# ARC-S-USB.net
KiCad netlist of a schematic drawn in Altium Designer
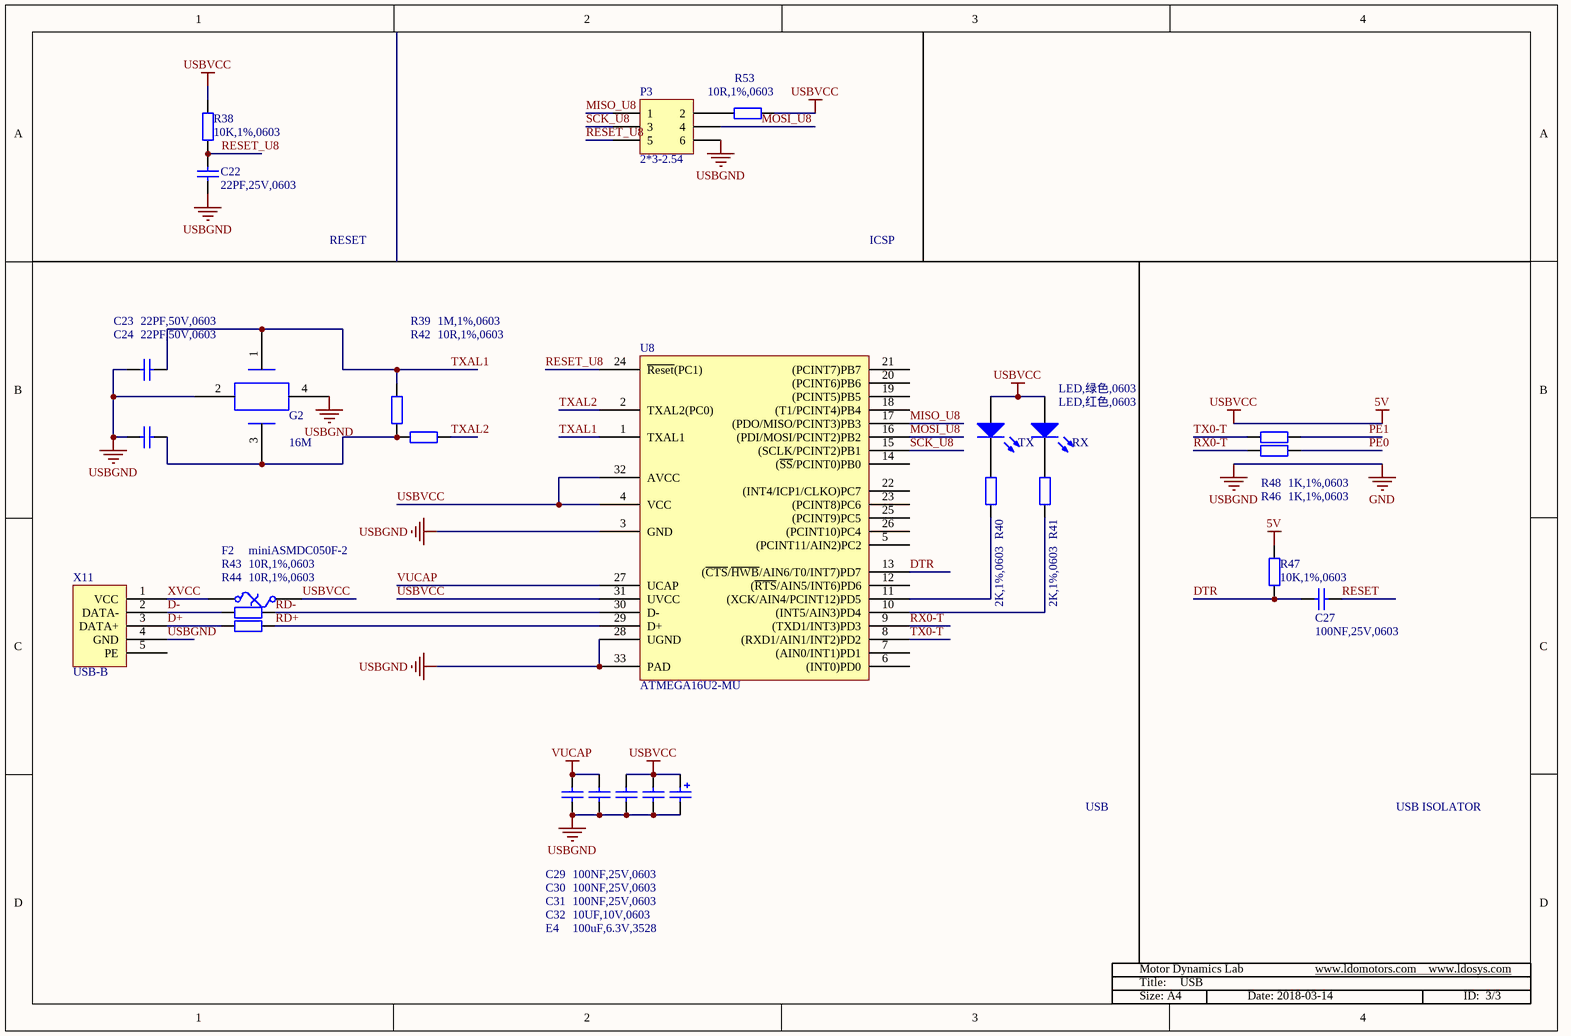
[diagram p0: ARC-S-USB.SchDoc]

(export (version "E")
  (design (tool "Eeschema 10.0.6"))
  (components
    (comp (ref "C22")
      (value "22PF,25V,0603")
      (footprint "RC0603")
      (description "Capacitor")
      (fields (field (name "PUBLISHER") "Altium Limited"))
      (libsource (lib "Miscellaneous Devices") (part "Cap"))
    )
    (comp (ref "C23")
      (value "22PF,50V,0603")
      (footprint "RC0603")
      (description "Capacitor")
      (fields (field (name "PUBLISHER") "Altium Limited"))
      (libsource (lib "Miscellaneous Devices") (part "Cap"))
    )
    (comp (ref "C24")
      (value "22PF,50V,0603")
      (footprint "RC0603")
      (description "Capacitor")
      (fields (field (name "PUBLISHER") "Altium Limited"))
      (libsource (lib "Miscellaneous Devices") (part "Cap"))
    )
    (comp (ref "C27")
      (value "100NF,25V,0603")
      (footprint "RC0603")
      (description "Capacitor")
      (fields (field (name "PUBLISHER") "Altium Limited"))
      (libsource (lib "Miscellaneous Devices") (part "Cap"))
    )
    (comp (ref "C29")
      (value "100NF,25V,0603")
      (footprint "RC0603")
      (description "Capacitor")
      (fields (field (name "PUBLISHER") "Altium Limited"))
      (libsource (lib "Miscellaneous Devices") (part "Cap"))
    )
    (comp (ref "C30")
      (value "100NF,25V,0603")
      (footprint "RC0603")
      (description "Capacitor")
      (fields (field (name "PUBLISHER") "Altium Limited"))
      (libsource (lib "Miscellaneous Devices") (part "Cap"))
    )
    (comp (ref "C31")
      (value "100NF,25V,0603")
      (footprint "RC0603")
      (description "Capacitor")
      (fields (field (name "PUBLISHER") "Altium Limited"))
      (libsource (lib "Miscellaneous Devices") (part "Cap"))
    )
    (comp (ref "C32")
      (value "10UF,10V,0603")
      (footprint "RC0603")
      (description "Capacitor")
      (fields (field (name "PUBLISHER") "Altium Limited"))
      (libsource (lib "Miscellaneous Devices") (part "Cap"))
    )
    (comp (ref "E4")
      (value "100uF,6.3V,3528")
      (footprint "3528-21")
      (description "Polarized Capacitor (Axial)")
      (fields (field (name "PUBLISHER") "Altium Limited"))
      (libsource (lib "Miscellaneous Devices") (part "Cap Pol2"))
    )
    (comp (ref "F2")
      (value "miniASMDC050F-2")
      (footprint "RC1812")
      (description "Thermal Fuse")
      (fields (field (name "PUBLISHER") "Altium Limited"))
      (libsource (lib "Miscellaneous Devices") (part "Fuse Thermal"))
    )
    (comp (ref "G2") (value "16M") (footprint "Y-3225") (libsource (lib "STM32F407VE") (part "G")))
    (comp (ref "P3")
      (value "2*3-2.54")
      (footprint "HDR2X3")
      (description "Header, 3-Pin, Dual row")
      (fields (field (name "PUBLISHER") "Altium Limited"))
      (libsource (lib "Miscellaneous Connectors") (part "Header 3X2"))
    )
    (comp (ref "R38")
      (value "10K,1%,0603")
      (footprint "RC0603")
      (description "Resistor")
      (fields (field (name "PUBLISHER") "Altium Limited"))
      (libsource (lib "") (part "Res2_3"))
    )
    (comp (ref "R39")
      (value "1M,1%,0603")
      (footprint "RC0603")
      (description "Resistor")
      (fields (field (name "PUBLISHER") "Altium Limited"))
      (libsource (lib "") (part "Res2_3"))
    )
    (comp (ref "R40")
      (value "2K,1%,0603")
      (footprint "RC0603")
      (description "Resistor")
      (fields (field (name "PUBLISHER") "Altium Limited"))
      (libsource (lib "") (part "Res2_3"))
    )
    (comp (ref "R41")
      (value "2K,1%,0603")
      (footprint "RC0603")
      (description "Resistor")
      (fields (field (name "PUBLISHER") "Altium Limited"))
      (libsource (lib "") (part "Res2_3"))
    )
    (comp (ref "R42")
      (value "10R,1%,0603")
      (footprint "RC0603")
      (description "Resistor")
      (fields (field (name "PUBLISHER") "Altium Limited"))
      (libsource (lib "Miscellaneous Devices") (part "Res2"))
    )
    (comp (ref "R43")
      (value "10R,1%,0603")
      (footprint "RC0603")
      (description "Resistor")
      (fields (field (name "PUBLISHER") "Altium Limited"))
      (libsource (lib "Miscellaneous Devices") (part "Res2"))
    )
    (comp (ref "R44")
      (value "10R,1%,0603")
      (footprint "RC0603")
      (description "Resistor")
      (fields (field (name "PUBLISHER") "Altium Limited"))
      (libsource (lib "Miscellaneous Devices") (part "Res2"))
    )
    (comp (ref "R46")
      (value "1K,1%,0603")
      (footprint "RC0603")
      (description "Resistor")
      (fields (field (name "PUBLISHER") "Altium Limited"))
      (libsource (lib "") (part "Res2_2"))
    )
    (comp (ref "R47")
      (value "10K,1%,0603")
      (footprint "RC0603")
      (description "Resistor")
      (fields (field (name "PUBLISHER") "Altium Limited"))
      (libsource (lib "") (part "Res2_1"))
    )
    (comp (ref "R48")
      (value "1K,1%,0603")
      (footprint "RC0603")
      (description "Resistor")
      (fields (field (name "PUBLISHER") "Altium Limited"))
      (libsource (lib "") (part "Res2_2"))
    )
    (comp (ref "R53")
      (value "10R,1%,0603")
      (footprint "RC0603")
      (description "Resistor")
      (fields (field (name "PUBLISHER") "Altium Limited"))
      (libsource (lib "") (part "Res2_2"))
    )
    (comp (ref "RX")
      (value "LED,红色,0603")
      (footprint "LED-0603")
      (description "Typical INFRARED GaAs LED")
      (fields (field (name "PUBLISHER") "Altium Limited"))
      (libsource (lib "Miscellaneous Devices") (part "LED0"))
    )
    (comp (ref "TX")
      (value "LED,绿色,0603")
      (footprint "LED-0603")
      (description "Typical INFRARED GaAs LED")
      (fields (field (name "PUBLISHER") "Altium Limited"))
      (libsource (lib "Miscellaneous Devices") (part "LED0"))
    )
    (comp (ref "U8")
      (value "ATMEGA16U2-MU")
      (footprint "QFN-32")
      (libsource (lib "LDO原理图库") (part "ATMEGA8U2-MU"))
    )
    (comp (ref "X11") (value "USB-B") (footprint "USB-B90") (libsource (lib "LDO原理图库") (part "B-USC")))
  )
  (nets
    (net (code "1") (name "/D+") (class "Default")
      (node (ref "R44") (pin "1") (pinfunction "1_1") (pintype "passive"))
      (node (ref "X11") (pin "3") (pinfunction "DATA+_3") (pintype "passive"))
    )
    (net (code "2") (name "/D-") (class "Default")
      (node (ref "R43") (pin "1") (pinfunction "1_1") (pintype "passive"))
      (node (ref "X11") (pin "2") (pinfunction "DATA-_2") (pintype "passive"))
    )
    (net (code "3") (name "/DTR") (class "Default")
      (node (ref "C27") (pin "2") (pinfunction "2_2") (pintype "passive"))
      (node (ref "R47") (pin "1") (pinfunction "1_1") (pintype "passive"))
      (node (ref "U8") (pin "13") (pinfunction "(~{CTS}/~{HWB}/AIN6/T0/INT7)PD7_13") (pintype "passive"))
    )
    (net (code "4") (name "/MISO_U8") (class "Default")
      (node (ref "P3") (pin "1") (pinfunction "1_1") (pintype "passive"))
      (node (ref "U8") (pin "17") (pinfunction "(PDO/MISO/PCINT3)PB3_17") (pintype "passive"))
    )
    (net (code "5") (name "/MOSI_U8") (class "Default")
      (node (ref "P3") (pin "4") (pinfunction "4_4") (pintype "passive"))
      (node (ref "U8") (pin "16") (pinfunction "(PDI/MOSI/PCINT2)PB2_16") (pintype "passive"))
    )
    (net (code "6") (name "/PE0") (class "Default")
      (node (ref "R46") (pin "1") (pinfunction "1_1") (pintype "passive"))
    )
    (net (code "7") (name "/PE1") (class "Default")
      (node (ref "R48") (pin "1") (pinfunction "1_1") (pintype "passive"))
    )
    (net (code "8") (name "/RD+") (class "Default")
      (node (ref "R44") (pin "2") (pinfunction "2_2") (pintype "passive"))
      (node (ref "U8") (pin "29") (pinfunction "D+_29") (pintype "passive"))
    )
    (net (code "9") (name "/RD-") (class "Default")
      (node (ref "R43") (pin "2") (pinfunction "2_2") (pintype "passive"))
      (node (ref "U8") (pin "30") (pinfunction "D-_30") (pintype "passive"))
    )
    (net (code "10") (name "/RESET") (class "Default")
      (node (ref "C27") (pin "1") (pinfunction "1_1") (pintype "passive"))
    )
    (net (code "11") (name "/RESET_U8") (class "Default")
      (node (ref "C22") (pin "1") (pinfunction "1_1") (pintype "passive"))
      (node (ref "P3") (pin "5") (pinfunction "5_5") (pintype "passive"))
      (node (ref "R38") (pin "2") (pinfunction "2_2") (pintype "passive"))
      (node (ref "U8") (pin "24") (pinfunction "~{Reset}(PC1)_24") (pintype "passive"))
    )
    (net (code "12") (name "/RX0-T") (class "Default")
      (node (ref "R46") (pin "2") (pinfunction "2_2") (pintype "passive"))
      (node (ref "U8") (pin "9") (pinfunction "(TXD1/INT3)PD3_9") (pintype "passive"))
    )
    (net (code "13") (name "/SCK_U8") (class "Default")
      (node (ref "P3") (pin "3") (pinfunction "3_3") (pintype "passive"))
      (node (ref "U8") (pin "15") (pinfunction "(SCLK/PCINT2)PB1_15") (pintype "passive"))
    )
    (net (code "14") (name "/TX0-T") (class "Default")
      (node (ref "R48") (pin "2") (pinfunction "2_2") (pintype "passive"))
      (node (ref "U8") (pin "8") (pinfunction "(RXD1/AIN1/INT2)PD2_8") (pintype "passive"))
    )
    (net (code "15") (name "/TXAL1") (class "Default")
      (node (ref "C23") (pin "1") (pinfunction "1_1") (pintype "passive"))
      (node (ref "G2") (pin "1") (pintype "passive"))
      (node (ref "R39") (pin "1") (pinfunction "1_1") (pintype "passive"))
      (node (ref "U8") (pin "1") (pinfunction "TXAL1_1") (pintype "passive"))
    )
    (net (code "16") (name "/TXAL2") (class "Default")
      (node (ref "R42") (pin "2") (pinfunction "2_2") (pintype "passive"))
      (node (ref "U8") (pin "2") (pinfunction "TXAL2(PC0)_2") (pintype "passive"))
    )
    (net (code "17") (name "/XVCC") (class "Default")
      (node (ref "F2") (pin "1") (pinfunction "1_1") (pintype "passive"))
      (node (ref "X11") (pin "1") (pinfunction "VCC_1") (pintype "passive"))
    )
    (net (code "18") (name "5V") (class "Default")
      (node (ref "C31") (pin "2") (pinfunction "2_2") (pintype "passive"))
      (node (ref "C32") (pin "2") (pinfunction "2_2") (pintype "passive"))
      (node (ref "E4") (pin "1") (pinfunction "1_1") (pintype "passive"))
      (node (ref "F2") (pin "2") (pinfunction "2_2") (pintype "passive"))
      (node (ref "R38") (pin "1") (pinfunction "1_1") (pintype "passive"))
      (node (ref "R47") (pin "2") (pinfunction "2_2") (pintype "passive"))
      (node (ref "R53") (pin "1") (pinfunction "1_1") (pintype "passive"))
      (node (ref "RX") (pin "1") (pinfunction "A_1") (pintype "passive"))
      (node (ref "TX") (pin "1") (pinfunction "A_1") (pintype "passive"))
      (node (ref "U8") (pin "31") (pinfunction "UVCC_31") (pintype "passive"))
      (node (ref "U8") (pin "32") (pinfunction "AVCC_32") (pintype "passive"))
      (node (ref "U8") (pin "4") (pinfunction "VCC_4") (pintype "passive"))
    )
    (net (code "19") (name "GND") (class "Default")
      (node (ref "C22") (pin "2") (pinfunction "2_2") (pintype "passive"))
      (node (ref "C23") (pin "2") (pinfunction "2_2") (pintype "passive"))
      (node (ref "C24") (pin "2") (pinfunction "2_2") (pintype "passive"))
      (node (ref "C29") (pin "1") (pinfunction "1_1") (pintype "passive"))
      (node (ref "C30") (pin "1") (pinfunction "1_1") (pintype "passive"))
      (node (ref "C31") (pin "1") (pinfunction "1_1") (pintype "passive"))
      (node (ref "C32") (pin "1") (pinfunction "1_1") (pintype "passive"))
      (node (ref "E4") (pin "2") (pinfunction "2_2") (pintype "passive"))
      (node (ref "G2") (pin "2") (pintype "passive"))
      (node (ref "G2") (pin "4") (pintype "passive"))
      (node (ref "P3") (pin "6") (pinfunction "6_6") (pintype "passive"))
      (node (ref "U8") (pin "28") (pinfunction "UGND_28") (pintype "passive"))
      (node (ref "U8") (pin "3") (pinfunction "GND_3") (pintype "passive"))
      (node (ref "U8") (pin "33") (pinfunction "PAD_33") (pintype "passive"))
      (node (ref "X11") (pin "4") (pinfunction "GND_4") (pintype "passive"))
    )
    (net (code "20") (name "Net-(C24-Pad1)") (class "Default")
      (node (ref "C24") (pin "1") (pinfunction "1_1") (pintype "passive"))
      (node (ref "G2") (pin "3") (pintype "passive"))
      (node (ref "R39") (pin "2") (pinfunction "2_2") (pintype "passive"))
      (node (ref "R42") (pin "1") (pinfunction "1_1") (pintype "passive"))
    )
    (net (code "21") (name "Net-(P3-Pad2)") (class "Default")
      (node (ref "P3") (pin "2") (pinfunction "2_2") (pintype "passive"))
      (node (ref "R53") (pin "2") (pinfunction "2_2") (pintype "passive"))
    )
    (net (code "22") (name "Net-(RX-K)") (class "Default")
      (node (ref "R41") (pin "1") (pinfunction "1_1") (pintype "passive"))
      (node (ref "RX") (pin "2") (pinfunction "K_2") (pintype "passive"))
    )
    (net (code "23") (name "Net-(TX-K)") (class "Default")
      (node (ref "R40") (pin "1") (pinfunction "1_1") (pintype "passive"))
      (node (ref "TX") (pin "2") (pinfunction "K_2") (pintype "passive"))
    )
    (net (code "24") (name "Net-(U8-(INT5{slash}AIN3)PD4)") (class "Default")
      (node (ref "R41") (pin "2") (pinfunction "2_2") (pintype "passive"))
      (node (ref "U8") (pin "10") (pinfunction "(INT5/AIN3)PD4_10") (pintype "passive"))
    )
    (net (code "25") (name "Net-(U8-(XCK{slash}AIN4{slash}PCINT12)PD5)") (class "Default")
      (node (ref "R40") (pin "2") (pinfunction "2_2") (pintype "passive"))
      (node (ref "U8") (pin "11") (pinfunction "(XCK/AIN4/PCINT12)PD5_11") (pintype "passive"))
    )
    (net (code "26") (name "VUCAP") (class "Default")
      (node (ref "C29") (pin "2") (pinfunction "2_2") (pintype "passive"))
      (node (ref "C30") (pin "2") (pinfunction "2_2") (pintype "passive"))
      (node (ref "U8") (pin "27") (pinfunction "UCAP_27") (pintype "passive"))
    )
    (net (code "27") (name "unconnected-(U8-(AIN0{slash}INT1)PD1-Pad7)") (class "Default")
      (node (ref "U8") (pin "7") (pinfunction "(AIN0/INT1)PD1_7") (pintype "passive"))
    )
    (net (code "28") (name "unconnected-(U8-(INT0)PD0-Pad6)") (class "Default")
      (node (ref "U8") (pin "6") (pinfunction "(INT0)PD0_6") (pintype "passive"))
    )
    (net (code "29") (name "unconnected-(U8-(INT4{slash}ICP1{slash}CLKO)PC7-Pad22)") (class "Default")
      (node (ref "U8") (pin "22") (pinfunction "(INT4/ICP1/CLKO)PC7_22") (pintype "passive"))
    )
    (net (code "30") (name "unconnected-(U8-(PCINT5)PB5-Pad19)") (class "Default")
      (node (ref "U8") (pin "19") (pinfunction "(PCINT5)PB5_19") (pintype "passive"))
    )
    (net (code "31") (name "unconnected-(U8-(PCINT6)PB6-Pad20)") (class "Default")
      (node (ref "U8") (pin "20") (pinfunction "(PCINT6)PB6_20") (pintype "passive"))
    )
    (net (code "32") (name "unconnected-(U8-(PCINT7)PB7-Pad21)") (class "Default")
      (node (ref "U8") (pin "21") (pinfunction "(PCINT7)PB7_21") (pintype "passive"))
    )
    (net (code "33") (name "unconnected-(U8-(PCINT8)PC6-Pad23)") (class "Default")
      (node (ref "U8") (pin "23") (pinfunction "(PCINT8)PC6_23") (pintype "passive"))
    )
    (net (code "34") (name "unconnected-(U8-(PCINT9)PC5-Pad25)") (class "Default")
      (node (ref "U8") (pin "25") (pinfunction "(PCINT9)PC5_25") (pintype "passive"))
    )
    (net (code "35") (name "unconnected-(U8-(PCINT10)PC4-Pad26)") (class "Default")
      (node (ref "U8") (pin "26") (pinfunction "(PCINT10)PC4_26") (pintype "passive"))
    )
    (net (code "36") (name "unconnected-(U8-(PCINT11{slash}AIN2)PC2-Pad5)") (class "Default")
      (node (ref "U8") (pin "5") (pinfunction "(PCINT11/AIN2)PC2_5") (pintype "passive"))
    )
    (net (code "37") (name "unconnected-(U8-(T1{slash}PCINT4)PB4-Pad18)") (class "Default")
      (node (ref "U8") (pin "18") (pinfunction "(T1/PCINT4)PB4_18") (pintype "passive"))
    )
    (net (code "38") (name "unconnected-(U8-(~{RTS}{slash}AIN5{slash}INT6)PD6-Pad12)") (class "Default")
      (node (ref "U8") (pin "12") (pinfunction "(~{RTS}/AIN5/INT6)PD6_12") (pintype "passive"))
    )
    (net (code "39") (name "unconnected-(U8-(~{SS}{slash}PCINT0)PB0-Pad14)") (class "Default")
      (node (ref "U8") (pin "14") (pinfunction "(~{SS}/PCINT0)PB0_14") (pintype "passive"))
    )
    (net (code "40") (name "unconnected-(X11-PE-Pad5)") (class "Default")
      (node (ref "X11") (pin "5") (pinfunction "PE_5") (pintype "passive"))
    )
  )
)
